# LSU_4_9_OpenAFR_Gauge.net
KiCad netlist of a schematic drawn in EAGLE
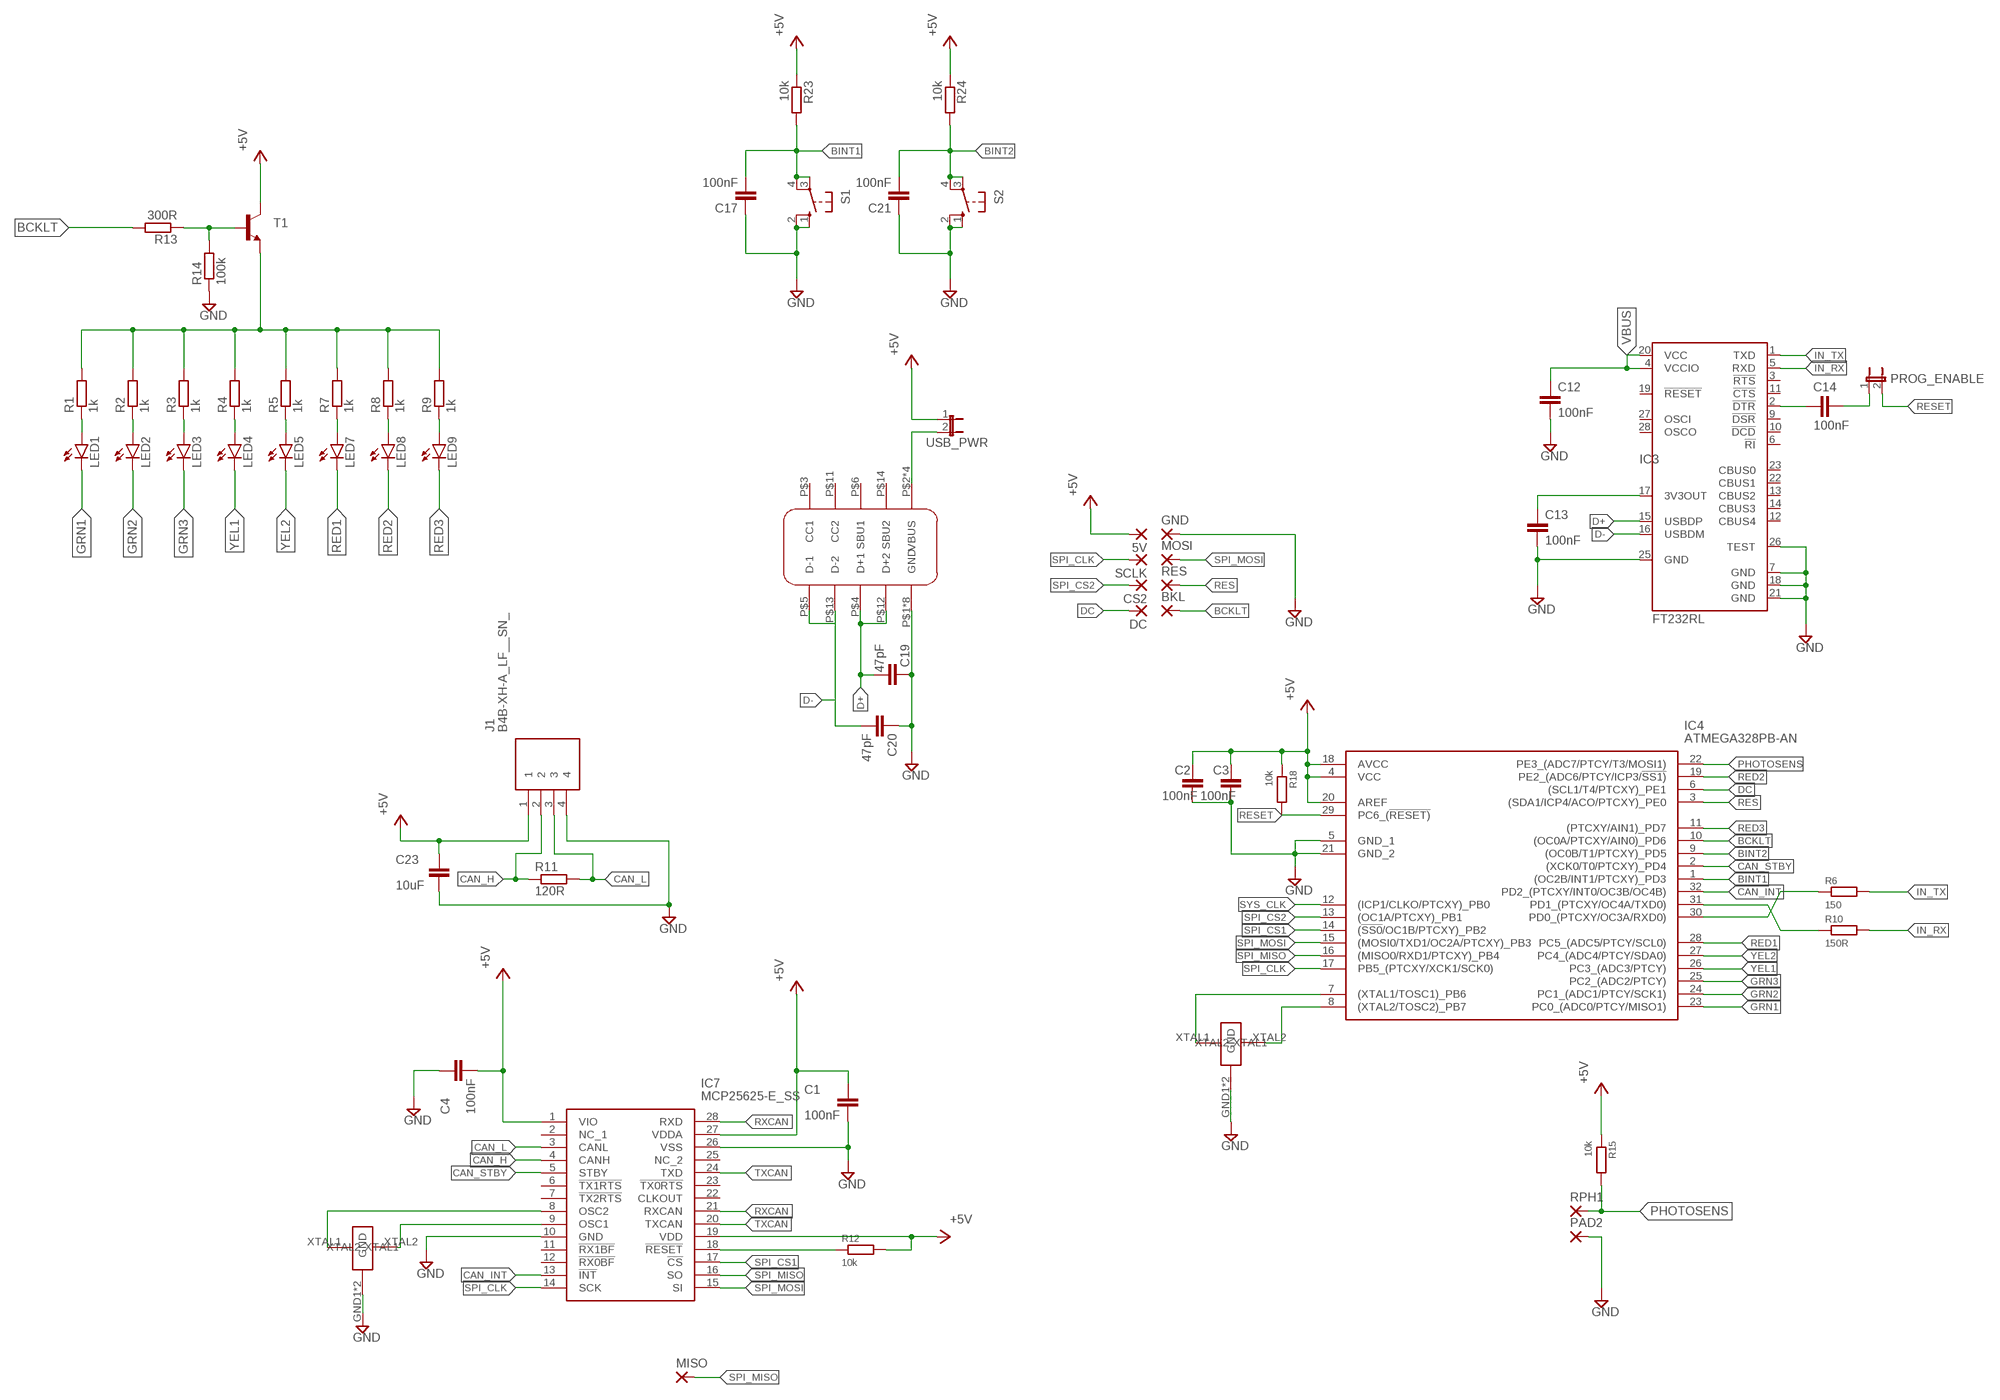
[diagram p0: schematic, sheet 1]

(export (version "E")
  (design (tool "Eeschema 10.0.6"))
  (components
    (comp (ref "5V")
      (value "1,6/0,9")
      (footprint "eagle-import:1,6_0,9")
      (libsource (lib "eagle-import") (part "1,6/0,9"))
    )
    (comp (ref "BKL")
      (value "1,6/0,9")
      (footprint "eagle-import:1,6_0,9")
      (libsource (lib "eagle-import") (part "1,6/0,9"))
    )
    (comp (ref "C1")
      (value "100nF")
      (footprint "eagle-import:C0805")
      (libsource (lib "eagle-import") (part "C-EUC0805"))
    )
    (comp (ref "C2")
      (value "100nF")
      (footprint "eagle-import:C0805")
      (libsource (lib "eagle-import") (part "C-EUC0805"))
    )
    (comp (ref "C3")
      (value "100nF")
      (footprint "eagle-import:C0805")
      (libsource (lib "eagle-import") (part "C-EUC0805"))
    )
    (comp (ref "C4")
      (value "100nF")
      (footprint "eagle-import:C0805")
      (libsource (lib "eagle-import") (part "C-EUC0805"))
    )
    (comp (ref "C12")
      (value "100nF")
      (footprint "eagle-import:C0805")
      (libsource (lib "eagle-import") (part "C-EUC0805"))
    )
    (comp (ref "C13")
      (value "100nF")
      (footprint "eagle-import:C0805")
      (libsource (lib "eagle-import") (part "C-EUC0805"))
    )
    (comp (ref "C14")
      (value "100nF")
      (footprint "eagle-import:C0805")
      (libsource (lib "eagle-import") (part "C-EUC0805"))
    )
    (comp (ref "C17")
      (value "100nF")
      (footprint "eagle-import:C0805")
      (libsource (lib "eagle-import") (part "C-EUC0805"))
    )
    (comp (ref "C19")
      (value "47pF")
      (footprint "eagle-import:C0805")
      (libsource (lib "eagle-import") (part "C-EUC0805"))
    )
    (comp (ref "C20")
      (value "47pF")
      (footprint "eagle-import:C0805")
      (libsource (lib "eagle-import") (part "C-EUC0805"))
    )
    (comp (ref "C21")
      (value "100nF")
      (footprint "eagle-import:C0805")
      (libsource (lib "eagle-import") (part "C-EUC0805"))
    )
    (comp (ref "C23")
      (value "10uF")
      (footprint "eagle-import:C0805")
      (libsource (lib "eagle-import") (part "C-EUC0805"))
    )
    (comp (ref "CS2")
      (value "1,6/0,9")
      (footprint "eagle-import:1,6_0,9")
      (libsource (lib "eagle-import") (part "1,6/0,9"))
    )
    (comp (ref "DC")
      (value "1,6/0,9")
      (footprint "eagle-import:1,6_0,9")
      (libsource (lib "eagle-import") (part "1,6/0,9"))
    )
    (comp (ref "GND")
      (value "1,6/0,9")
      (footprint "eagle-import:1,6_0,9")
      (libsource (lib "eagle-import") (part "1,6/0,9"))
    )
    (comp (ref "IC3")
      (value "FT232RL")
      (footprint "eagle-import:SSOP28")
      (libsource (lib "eagle-import") (part "FT232RL"))
    )
    (comp (ref "IC4")
      (value "ATMEGA328PB-AN")
      (footprint "eagle-import:QFP80P900X900X120-32N")
      (fields (field (name "MOUSER_PART_NUMBER") "556-ATMEGA328PB-AN"))
      (libsource (lib "eagle-import") (part "ATMEGA328PB-AN"))
    )
    (comp (ref "IC7")
      (value "MCP25625-E_SS")
      (footprint "eagle-import:SOP65P780X200-28N")
      (fields
        (field (name "MANUFACTURER_PART_NUMBER") "MCP25625-E/SS")
        (field (name "MOUSER_PART_NUMBER") "579-MCP25625-E/SS")
      )
      (libsource (lib "eagle-import") (part "MCP25625-E_SS"))
    )
    (comp (ref "J1")
      (value "B4B-XH-A_LF__SN_")
      (footprint "eagle-import:B4BXHALFSN")
      (fields
        (field (name "MANUFACTURER_PART_NUMBER") "B4B-XH-A(LF)(SN)")
        (field (name "MOUSER_PART_NUMBER") "306-B4BXHALFSN")
      )
      (libsource (lib "eagle-import") (part "B4B-XH-A_LF__SN_"))
    )
    (comp (ref "LED1")
      (value "LEDCHIPLED_1206")
      (footprint "eagle-import:CHIPLED_1206")
      (libsource (lib "eagle-import") (part "LEDCHIPLED_1206"))
    )
    (comp (ref "LED2")
      (value "LEDCHIPLED_1206")
      (footprint "eagle-import:CHIPLED_1206")
      (libsource (lib "eagle-import") (part "LEDCHIPLED_1206"))
    )
    (comp (ref "LED3")
      (value "LEDCHIPLED_1206")
      (footprint "eagle-import:CHIPLED_1206")
      (libsource (lib "eagle-import") (part "LEDCHIPLED_1206"))
    )
    (comp (ref "LED4")
      (value "LEDCHIPLED_1206")
      (footprint "eagle-import:CHIPLED_1206")
      (libsource (lib "eagle-import") (part "LEDCHIPLED_1206"))
    )
    (comp (ref "LED5")
      (value "LEDCHIPLED_1206")
      (footprint "eagle-import:CHIPLED_1206")
      (libsource (lib "eagle-import") (part "LEDCHIPLED_1206"))
    )
    (comp (ref "LED7")
      (value "LEDCHIPLED_1206")
      (footprint "eagle-import:CHIPLED_1206")
      (libsource (lib "eagle-import") (part "LEDCHIPLED_1206"))
    )
    (comp (ref "LED8")
      (value "LEDCHIPLED_1206")
      (footprint "eagle-import:CHIPLED_1206")
      (libsource (lib "eagle-import") (part "LEDCHIPLED_1206"))
    )
    (comp (ref "LED9")
      (value "LEDCHIPLED_1206")
      (footprint "eagle-import:CHIPLED_1206")
      (libsource (lib "eagle-import") (part "LEDCHIPLED_1206"))
    )
    (comp (ref "MISO")
      (value "1,6/0,9")
      (footprint "eagle-import:1,6_0,9")
      (libsource (lib "eagle-import") (part "1,6/0,9"))
    )
    (comp (ref "MOSI")
      (value "1,6/0,9")
      (footprint "eagle-import:1,6_0,9")
      (libsource (lib "eagle-import") (part "1,6/0,9"))
    )
    (comp (ref "PAD2")
      (value "1,6/0,8")
      (footprint "eagle-import:1,6_0,8")
      (libsource (lib "eagle-import") (part "1,6/0,8"))
    )
    (comp (ref "PROG_ENABLE")
      (value "JP1E")
      (footprint "eagle-import:JP1")
      (libsource (lib "eagle-import") (part "JP1E"))
    )
    (comp (ref "R1")
      (value "1k")
      (footprint "eagle-import:R0805")
      (libsource (lib "eagle-import") (part "R-EU_R0805"))
    )
    (comp (ref "R2")
      (value "1k")
      (footprint "eagle-import:R0805")
      (libsource (lib "eagle-import") (part "R-EU_R0805"))
    )
    (comp (ref "R3")
      (value "1k")
      (footprint "eagle-import:R0805")
      (libsource (lib "eagle-import") (part "R-EU_R0805"))
    )
    (comp (ref "R4")
      (value "1k")
      (footprint "eagle-import:R0805")
      (libsource (lib "eagle-import") (part "R-EU_R0805"))
    )
    (comp (ref "R5")
      (value "1k")
      (footprint "eagle-import:R0805")
      (libsource (lib "eagle-import") (part "R-EU_R0805"))
    )
    (comp (ref "R6")
      (value "150")
      (footprint "eagle-import:R0805")
      (libsource (lib "eagle-import") (part "R-EU_R0805"))
    )
    (comp (ref "R7")
      (value "1k")
      (footprint "eagle-import:R0805")
      (libsource (lib "eagle-import") (part "R-EU_R0805"))
    )
    (comp (ref "R8")
      (value "1k")
      (footprint "eagle-import:R0805")
      (libsource (lib "eagle-import") (part "R-EU_R0805"))
    )
    (comp (ref "R9")
      (value "1k")
      (footprint "eagle-import:R0805")
      (libsource (lib "eagle-import") (part "R-EU_R0805"))
    )
    (comp (ref "R10")
      (value "150R")
      (footprint "eagle-import:R0805")
      (libsource (lib "eagle-import") (part "R-EU_R0805"))
    )
    (comp (ref "R11")
      (value "120R")
      (footprint "eagle-import:R1206")
      (libsource (lib "eagle-import") (part "R-EU_R1206"))
    )
    (comp (ref "R12")
      (value "10k")
      (footprint "eagle-import:R0805")
      (libsource (lib "eagle-import") (part "R-EU_R0805"))
    )
    (comp (ref "R13")
      (value "300R")
      (footprint "eagle-import:R0805")
      (libsource (lib "eagle-import") (part "R-EU_R0805"))
    )
    (comp (ref "R14")
      (value "100k")
      (footprint "eagle-import:R0805")
      (libsource (lib "eagle-import") (part "R-EU_R0805"))
    )
    (comp (ref "R15")
      (value "10k")
      (footprint "eagle-import:R0805")
      (libsource (lib "eagle-import") (part "R-EU_R0805"))
    )
    (comp (ref "R18")
      (value "10k")
      (footprint "eagle-import:R0805")
      (libsource (lib "eagle-import") (part "R-EU_R0805"))
    )
    (comp (ref "R23")
      (value "10k")
      (footprint "eagle-import:R0805")
      (libsource (lib "eagle-import") (part "R-EU_R0805"))
    )
    (comp (ref "R24")
      (value "10k")
      (footprint "eagle-import:R0805")
      (libsource (lib "eagle-import") (part "R-EU_R0805"))
    )
    (comp (ref "RES")
      (value "1,6/0,9")
      (footprint "eagle-import:1,6_0,9")
      (libsource (lib "eagle-import") (part "1,6/0,9"))
    )
    (comp (ref "RPH1")
      (value "1,6/0,8")
      (footprint "eagle-import:1,6_0,8")
      (libsource (lib "eagle-import") (part "1,6/0,8"))
    )
    (comp (ref "S1")
      (value "10-XX")
      (footprint "eagle-import:B3F-10XX")
      (fields (field (name "MPN") "B3F-1000"))
      (libsource (lib "eagle-import") (part "10-XX"))
    )
    (comp (ref "S2")
      (value "10-XX")
      (footprint "eagle-import:B3F-10XX")
      (fields (field (name "MPN") "B3F-1000"))
      (libsource (lib "eagle-import") (part "10-XX"))
    )
    (comp (ref "SCLK")
      (value "1,6/0,9")
      (footprint "eagle-import:1,6_0,9")
      (libsource (lib "eagle-import") (part "1,6/0,9"))
    )
    (comp (ref "T1")
      (value "BC817-16-NPN-SOT23-BEC")
      (footprint "eagle-import:SOT23-BEC")
      (libsource (lib "eagle-import") (part "-NPN-SOT23-BECBC817-16"))
    )
    (comp (ref "U$1")
      (value "USBC-2.0-THT")
      (footprint "eagle-import:USBC-2.0-THT")
      (libsource (lib "eagle-import") (part "USBC-2.0-THT"))
    )
    (comp (ref "U$2")
      (value "E3X160181X04")
      (footprint "eagle-import:E3X160181X04")
      (libsource (lib "eagle-import") (part "E3X160181X04"))
    )
    (comp (ref "U$3")
      (value "E3X160181X04")
      (footprint "eagle-import:E3X160181X04")
      (libsource (lib "eagle-import") (part "E3X160181X04"))
    )
    (comp (ref "USB_PWR")
      (value "JP1E")
      (footprint "eagle-import:JP1")
      (libsource (lib "eagle-import") (part "JP1E"))
    )
  )
  (nets
    (net (code "1") (name "+5V") (class "Default")
      (node (ref "5V") (pin "1") (pinfunction "P_1") (pintype "passive"))
      (node (ref "C1") (pin "1") (pinfunction "1_1") (pintype "passive"))
      (node (ref "C2") (pin "1") (pinfunction "1_1") (pintype "passive"))
      (node (ref "C23") (pin "1") (pinfunction "1_1") (pintype "passive"))
      (node (ref "C3") (pin "1") (pinfunction "1_1") (pintype "passive"))
      (node (ref "C4") (pin "2") (pinfunction "2_2") (pintype "passive"))
      (node (ref "IC4") (pin "18") (pinfunction "AVCC_18") (pintype "bidirectional"))
      (node (ref "IC4") (pin "20") (pinfunction "AREF_20") (pintype "bidirectional"))
      (node (ref "IC4") (pin "4") (pinfunction "VCC_4") (pintype "bidirectional"))
      (node (ref "IC7") (pin "1") (pinfunction "VIO_1") (pintype "bidirectional"))
      (node (ref "IC7") (pin "19") (pinfunction "VDD_19") (pintype "bidirectional"))
      (node (ref "IC7") (pin "27") (pinfunction "VDDA_27") (pintype "bidirectional"))
      (node (ref "J1") (pin "1") (pinfunction "1_1") (pintype "bidirectional"))
      (node (ref "R12") (pin "2") (pinfunction "2_2") (pintype "passive"))
      (node (ref "R15") (pin "1") (pinfunction "1_1") (pintype "passive"))
      (node (ref "R18") (pin "1") (pinfunction "1_1") (pintype "passive"))
      (node (ref "R23") (pin "1") (pinfunction "1_1") (pintype "passive"))
      (node (ref "R24") (pin "1") (pinfunction "1_1") (pintype "passive"))
      (node (ref "T1") (pin "C") (pinfunction "C_C") (pintype "passive"))
      (node (ref "USB_PWR") (pin "1") (pinfunction "1_1") (pintype "passive"))
    )
    (net (code "2") (name "BCKLT") (class "Default")
      (node (ref "BKL") (pin "1") (pinfunction "P_1") (pintype "passive"))
      (node (ref "IC4") (pin "10") (pinfunction "(OC0A/PTCXY/AIN0)_PD6_10") (pintype "bidirectional"))
      (node (ref "R13") (pin "2") (pinfunction "2_2") (pintype "passive"))
    )
    (net (code "3") (name "BINT1") (class "Default")
      (node (ref "C17") (pin "2") (pinfunction "2_2") (pintype "passive"))
      (node (ref "IC4") (pin "1") (pinfunction "(OC2B/INT1/PTCXY)_PD3_1") (pintype "bidirectional"))
      (node (ref "R23") (pin "2") (pinfunction "2_2") (pintype "passive"))
      (node (ref "S1") (pin "3") (pinfunction "P_3") (pintype "passive"))
      (node (ref "S1") (pin "4") (pinfunction "P1_4") (pintype "passive"))
    )
    (net (code "4") (name "BINT2") (class "Default")
      (node (ref "C21") (pin "2") (pinfunction "2_2") (pintype "passive"))
      (node (ref "IC4") (pin "9") (pinfunction "(OC0B/T1/PTCXY)_PD5_9") (pintype "bidirectional"))
      (node (ref "R24") (pin "2") (pinfunction "2_2") (pintype "passive"))
      (node (ref "S2") (pin "3") (pinfunction "P_3") (pintype "passive"))
      (node (ref "S2") (pin "4") (pinfunction "P1_4") (pintype "passive"))
    )
    (net (code "5") (name "CAN_H") (class "Default")
      (node (ref "IC7") (pin "4") (pinfunction "CANH_4") (pintype "bidirectional"))
      (node (ref "J1") (pin "2") (pinfunction "2_2") (pintype "bidirectional"))
      (node (ref "R11") (pin "1") (pinfunction "1_1") (pintype "passive"))
    )
    (net (code "6") (name "CAN_INT") (class "Default")
      (node (ref "IC4") (pin "32") (pinfunction "PD2_(PTCXY/INT0/OC3B/OC4B)_32") (pintype "bidirectional"))
      (node (ref "IC7") (pin "13") (pinfunction "~{INT}_13") (pintype "bidirectional"))
    )
    (net (code "7") (name "CAN_L") (class "Default")
      (node (ref "IC7") (pin "3") (pinfunction "CANL_3") (pintype "bidirectional"))
      (node (ref "J1") (pin "3") (pinfunction "3_3") (pintype "bidirectional"))
      (node (ref "R11") (pin "2") (pinfunction "2_2") (pintype "passive"))
    )
    (net (code "8") (name "CAN_STBY") (class "Default")
      (node (ref "IC4") (pin "2") (pinfunction "(XCK0/T0/PTCXY)_PD4_2") (pintype "bidirectional"))
      (node (ref "IC7") (pin "5") (pinfunction "STBY_5") (pintype "bidirectional"))
    )
    (net (code "9") (name "D+") (class "Default")
      (node (ref "C19") (pin "2") (pinfunction "2_2") (pintype "passive"))
      (node (ref "IC3") (pin "15") (pinfunction "USBDP_15") (pintype "bidirectional"))
      (node (ref "U$1") (pin "P$12") (pinfunction "D+2_P$12") (pintype "bidirectional"))
      (node (ref "U$1") (pin "P$4") (pinfunction "D+1_P$4") (pintype "bidirectional"))
    )
    (net (code "10") (name "D-") (class "Default")
      (node (ref "C20") (pin "2") (pinfunction "2_2") (pintype "passive"))
      (node (ref "IC3") (pin "16") (pinfunction "USBDM_16") (pintype "bidirectional"))
      (node (ref "U$1") (pin "P$13") (pinfunction "D-2_P$13") (pintype "bidirectional"))
      (node (ref "U$1") (pin "P$5") (pinfunction "D-1_P$5") (pintype "bidirectional"))
    )
    (net (code "11") (name "DC") (class "Default")
      (node (ref "DC") (pin "1") (pinfunction "P_1") (pintype "passive"))
      (node (ref "IC4") (pin "6") (pinfunction "(SCL1/T4/PTCXY)_PE1_6") (pintype "bidirectional"))
    )
    (net (code "12") (name "GND") (class "Default")
      (node (ref "C1") (pin "2") (pinfunction "2_2") (pintype "passive"))
      (node (ref "C12") (pin "2") (pinfunction "2_2") (pintype "passive"))
      (node (ref "C13") (pin "2") (pinfunction "2_2") (pintype "passive"))
      (node (ref "C17") (pin "1") (pinfunction "1_1") (pintype "passive"))
      (node (ref "C19") (pin "1") (pinfunction "1_1") (pintype "passive"))
      (node (ref "C2") (pin "2") (pinfunction "2_2") (pintype "passive"))
      (node (ref "C20") (pin "1") (pinfunction "1_1") (pintype "passive"))
      (node (ref "C21") (pin "1") (pinfunction "1_1") (pintype "passive"))
      (node (ref "C23") (pin "2") (pinfunction "2_2") (pintype "passive"))
      (node (ref "C3") (pin "2") (pinfunction "2_2") (pintype "passive"))
      (node (ref "C4") (pin "1") (pinfunction "1_1") (pintype "passive"))
      (node (ref "GND") (pin "1") (pinfunction "P_1") (pintype "passive"))
      (node (ref "IC3") (pin "18") (pinfunction "GND_18") (pintype "power_in"))
      (node (ref "IC3") (pin "21") (pinfunction "GND_21") (pintype "power_in"))
      (node (ref "IC3") (pin "25") (pinfunction "GND_25") (pintype "power_in"))
      (node (ref "IC3") (pin "26") (pinfunction "TEST_26") (pintype "input"))
      (node (ref "IC3") (pin "7") (pinfunction "GND_7") (pintype "power_in"))
      (node (ref "IC4") (pin "21") (pinfunction "GND_2_21") (pintype "bidirectional"))
      (node (ref "IC4") (pin "5") (pinfunction "GND_1_5") (pintype "bidirectional"))
      (node (ref "IC7") (pin "10") (pinfunction "GND_10") (pintype "bidirectional"))
      (node (ref "IC7") (pin "26") (pinfunction "VSS_26") (pintype "bidirectional"))
      (node (ref "J1") (pin "4") (pinfunction "4_4") (pintype "bidirectional"))
      (node (ref "PAD2") (pin "1") (pinfunction "P_1") (pintype "passive"))
      (node (ref "R14") (pin "1") (pinfunction "1_1") (pintype "passive"))
      (node (ref "S1") (pin "1") (pinfunction "S_1") (pintype "passive"))
      (node (ref "S1") (pin "2") (pinfunction "S1_2") (pintype "passive"))
      (node (ref "S2") (pin "1") (pinfunction "S_1") (pintype "passive"))
      (node (ref "S2") (pin "2") (pinfunction "S1_2") (pintype "passive"))
      (node (ref "U$1") (pin "P$1") (pinfunction "GND_P$1") (pintype "bidirectional"))
      (node (ref "U$1") (pin "P$16") (pinfunction "GND_P$16") (pintype "bidirectional"))
      (node (ref "U$1") (pin "P$17") (pinfunction "GND_P$17") (pintype "bidirectional"))
      (node (ref "U$1") (pin "P$18") (pinfunction "GND_P$18") (pintype "bidirectional"))
      (node (ref "U$1") (pin "P$19") (pinfunction "GND_P$19") (pintype "bidirectional"))
      (node (ref "U$1") (pin "P$20") (pinfunction "GND_P$20") (pintype "bidirectional"))
      (node (ref "U$1") (pin "P$8") (pinfunction "GND_P$8") (pintype "bidirectional"))
      (node (ref "U$1") (pin "P$9") (pinfunction "GND_P$9") (pintype "bidirectional"))
      (node (ref "U$2") (pin "GND1") (pinfunction "GND_GND1") (pintype "bidirectional"))
      (node (ref "U$2") (pin "GND2") (pinfunction "GND_GND2") (pintype "bidirectional"))
      (node (ref "U$3") (pin "GND1") (pinfunction "GND_GND1") (pintype "bidirectional"))
      (node (ref "U$3") (pin "GND2") (pinfunction "GND_GND2") (pintype "bidirectional"))
    )
    (net (code "13") (name "GRN1") (class "Default")
      (node (ref "IC4") (pin "23") (pinfunction "PC0_(ADC0/PTCY/MISO1)_23") (pintype "bidirectional"))
      (node (ref "LED1") (pin "C") (pinfunction "C_C") (pintype "passive"))
    )
    (net (code "14") (name "GRN2") (class "Default")
      (node (ref "IC4") (pin "24") (pinfunction "PC1_(ADC1/PTCY/SCK1)_24") (pintype "bidirectional"))
      (node (ref "LED2") (pin "C") (pinfunction "C_C") (pintype "passive"))
    )
    (net (code "15") (name "GRN3") (class "Default")
      (node (ref "IC4") (pin "25") (pinfunction "PC2_(ADC2/PTCY)_25") (pintype "bidirectional"))
      (node (ref "LED3") (pin "C") (pinfunction "C_C") (pintype "passive"))
    )
    (net (code "16") (name "IN_RX") (class "Default")
      (node (ref "IC3") (pin "5") (pinfunction "RXD_5") (pintype "input"))
      (node (ref "R10") (pin "2") (pinfunction "2_2") (pintype "passive"))
    )
    (net (code "17") (name "IN_TX") (class "Default")
      (node (ref "IC3") (pin "1") (pinfunction "TXD_1") (pintype "output"))
      (node (ref "R6") (pin "2") (pinfunction "2_2") (pintype "passive"))
    )
    (net (code "18") (name "Net-(C14-Pad2)") (class "Default")
      (node (ref "C14") (pin "2") (pinfunction "2_2") (pintype "passive"))
      (node (ref "PROG_ENABLE") (pin "1") (pinfunction "1_1") (pintype "passive"))
    )
    (net (code "19") (name "Net-(IC3-3V3OUT)") (class "Default")
      (node (ref "C13") (pin "1") (pinfunction "1_1") (pintype "passive"))
      (node (ref "IC3") (pin "17") (pinfunction "3V3OUT_17") (pintype "output"))
    )
    (net (code "20") (name "Net-(IC3-~{DTR})") (class "Default")
      (node (ref "C14") (pin "1") (pinfunction "1_1") (pintype "passive"))
      (node (ref "IC3") (pin "2") (pinfunction "~{DTR}_2") (pintype "output"))
    )
    (net (code "21") (name "Net-(IC4-(XTAL1{slash}TOSC1)_PB6)") (class "Default")
      (node (ref "IC4") (pin "7") (pinfunction "(XTAL1/TOSC1)_PB6_7") (pintype "bidirectional"))
      (node (ref "U$3") (pin "XTAL1") (pinfunction "XTAL1_XTAL1") (pintype "bidirectional"))
    )
    (net (code "22") (name "Net-(IC4-(XTAL2{slash}TOSC2)_PB7)") (class "Default")
      (node (ref "IC4") (pin "8") (pinfunction "(XTAL2/TOSC2)_PB7_8") (pintype "bidirectional"))
      (node (ref "U$3") (pin "XTAL2") (pinfunction "XTAL2_XTAL2") (pintype "bidirectional"))
    )
    (net (code "23") (name "Net-(IC4-PD0_(PTCXY{slash}OC3A{slash}RXD0))") (class "Default")
      (node (ref "IC4") (pin "30") (pinfunction "PD0_(PTCXY/OC3A/RXD0)_30") (pintype "bidirectional"))
      (node (ref "R6") (pin "1") (pinfunction "1_1") (pintype "passive"))
    )
    (net (code "24") (name "Net-(IC4-PD1_(PTCXY{slash}OC4A{slash}TXD0))") (class "Default")
      (node (ref "IC4") (pin "31") (pinfunction "PD1_(PTCXY/OC4A/TXD0)_31") (pintype "bidirectional"))
      (node (ref "R10") (pin "1") (pinfunction "1_1") (pintype "passive"))
    )
    (net (code "25") (name "Net-(IC7-OSC1)") (class "Default")
      (node (ref "IC7") (pin "9") (pinfunction "OSC1_9") (pintype "bidirectional"))
      (node (ref "U$2") (pin "XTAL2") (pinfunction "XTAL2_XTAL2") (pintype "bidirectional"))
    )
    (net (code "26") (name "Net-(IC7-OSC2)") (class "Default")
      (node (ref "IC7") (pin "8") (pinfunction "OSC2_8") (pintype "bidirectional"))
      (node (ref "U$2") (pin "XTAL1") (pinfunction "XTAL1_XTAL1") (pintype "bidirectional"))
    )
    (net (code "27") (name "Net-(IC7-~{RESET})") (class "Default")
      (node (ref "IC7") (pin "18") (pinfunction "~{RESET}_18") (pintype "bidirectional"))
      (node (ref "R12") (pin "1") (pinfunction "1_1") (pintype "passive"))
    )
    (net (code "28") (name "Net-(LED1-PadA)") (class "Default")
      (node (ref "LED1") (pin "A") (pinfunction "A_A") (pintype "passive"))
      (node (ref "R1") (pin "1") (pinfunction "1_1") (pintype "passive"))
    )
    (net (code "29") (name "Net-(LED2-PadA)") (class "Default")
      (node (ref "LED2") (pin "A") (pinfunction "A_A") (pintype "passive"))
      (node (ref "R2") (pin "1") (pinfunction "1_1") (pintype "passive"))
    )
    (net (code "30") (name "Net-(LED3-PadA)") (class "Default")
      (node (ref "LED3") (pin "A") (pinfunction "A_A") (pintype "passive"))
      (node (ref "R3") (pin "1") (pinfunction "1_1") (pintype "passive"))
    )
    (net (code "31") (name "Net-(LED4-PadA)") (class "Default")
      (node (ref "LED4") (pin "A") (pinfunction "A_A") (pintype "passive"))
      (node (ref "R4") (pin "1") (pinfunction "1_1") (pintype "passive"))
    )
    (net (code "32") (name "Net-(LED5-PadA)") (class "Default")
      (node (ref "LED5") (pin "A") (pinfunction "A_A") (pintype "passive"))
      (node (ref "R5") (pin "1") (pinfunction "1_1") (pintype "passive"))
    )
    (net (code "33") (name "Net-(LED7-PadA)") (class "Default")
      (node (ref "LED7") (pin "A") (pinfunction "A_A") (pintype "passive"))
      (node (ref "R7") (pin "1") (pinfunction "1_1") (pintype "passive"))
    )
    (net (code "34") (name "Net-(LED8-PadA)") (class "Default")
      (node (ref "LED8") (pin "A") (pinfunction "A_A") (pintype "passive"))
      (node (ref "R8") (pin "1") (pinfunction "1_1") (pintype "passive"))
    )
    (net (code "35") (name "Net-(LED9-PadA)") (class "Default")
      (node (ref "LED9") (pin "A") (pinfunction "A_A") (pintype "passive"))
      (node (ref "R9") (pin "1") (pinfunction "1_1") (pintype "passive"))
    )
    (net (code "36") (name "Net-(R1-Pad2)") (class "Default")
      (node (ref "R1") (pin "2") (pinfunction "2_2") (pintype "passive"))
      (node (ref "R2") (pin "2") (pinfunction "2_2") (pintype "passive"))
      (node (ref "R3") (pin "2") (pinfunction "2_2") (pintype "passive"))
      (node (ref "R4") (pin "2") (pinfunction "2_2") (pintype "passive"))
      (node (ref "R5") (pin "2") (pinfunction "2_2") (pintype "passive"))
      (node (ref "R7") (pin "2") (pinfunction "2_2") (pintype "passive"))
      (node (ref "R8") (pin "2") (pinfunction "2_2") (pintype "passive"))
      (node (ref "R9") (pin "2") (pinfunction "2_2") (pintype "passive"))
      (node (ref "T1") (pin "E") (pinfunction "E_E") (pintype "passive"))
    )
    (net (code "37") (name "Net-(R13-Pad1)") (class "Default")
      (node (ref "R13") (pin "1") (pinfunction "1_1") (pintype "passive"))
      (node (ref "R14") (pin "2") (pinfunction "2_2") (pintype "passive"))
      (node (ref "T1") (pin "B") (pinfunction "B_B") (pintype "passive"))
    )
    (net (code "38") (name "PHOTOSENS") (class "Default")
      (node (ref "IC4") (pin "22") (pinfunction "PE3_(ADC7/PTCY/T3/MOSI1)_22") (pintype "bidirectional"))
      (node (ref "R15") (pin "2") (pinfunction "2_2") (pintype "passive"))
      (node (ref "RPH1") (pin "1") (pinfunction "P_1") (pintype "passive"))
    )
    (net (code "39") (name "RED1") (class "Default")
      (node (ref "IC4") (pin "28") (pinfunction "PC5_(ADC5/PTCY/SCL0)_28") (pintype "bidirectional"))
      (node (ref "LED7") (pin "C") (pinfunction "C_C") (pintype "passive"))
    )
    (net (code "40") (name "RED2") (class "Default")
      (node (ref "IC4") (pin "19") (pinfunction "PE2_(ADC6/PTCY/ICP3/~{SS1})_19") (pintype "bidirectional"))
      (node (ref "LED8") (pin "C") (pinfunction "C_C") (pintype "passive"))
    )
    (net (code "41") (name "RED3") (class "Default")
      (node (ref "IC4") (pin "11") (pinfunction "(PTCXY/AIN1)_PD7_11") (pintype "bidirectional"))
      (node (ref "LED9") (pin "C") (pinfunction "C_C") (pintype "passive"))
    )
    (net (code "42") (name "RES") (class "Default")
      (node (ref "IC4") (pin "3") (pinfunction "(SDA1/ICP4/ACO/PTCXY)_PE0_3") (pintype "bidirectional"))
      (node (ref "RES") (pin "1") (pinfunction "P_1") (pintype "passive"))
    )
    (net (code "43") (name "RESET") (class "Default")
      (node (ref "IC4") (pin "29") (pinfunction "PC6_(~{RESET})_29") (pintype "bidirectional"))
      (node (ref "PROG_ENABLE") (pin "2") (pinfunction "2_2") (pintype "passive"))
      (node (ref "R18") (pin "2") (pinfunction "2_2") (pintype "passive"))
    )
    (net (code "44") (name "RXCAN") (class "Default")
      (node (ref "IC7") (pin "21") (pinfunction "RXCAN_21") (pintype "bidirectional"))
      (node (ref "IC7") (pin "28") (pinfunction "RXD_28") (pintype "bidirectional"))
    )
    (net (code "45") (name "SPI_CLK") (class "Default")
      (node (ref "IC4") (pin "17") (pinfunction "PB5_(PTCXY/XCK1/SCK0)_17") (pintype "bidirectional"))
      (node (ref "IC7") (pin "14") (pinfunction "SCK_14") (pintype "bidirectional"))
      (node (ref "SCLK") (pin "1") (pinfunction "P_1") (pintype "passive"))
    )
    (net (code "46") (name "SPI_CS1") (class "Default")
      (node (ref "IC4") (pin "14") (pinfunction "(~{SS0}/OC1B/PTCXY)_PB2_14") (pintype "bidirectional"))
      (node (ref "IC7") (pin "17") (pinfunction "~{CS}_17") (pintype "bidirectional"))
    )
    (net (code "47") (name "SPI_CS2") (class "Default")
      (node (ref "CS2") (pin "1") (pinfunction "P_1") (pintype "passive"))
      (node (ref "IC4") (pin "13") (pinfunction "(OC1A/PTCXY)_PB1_13") (pintype "bidirectional"))
    )
    (net (code "48") (name "SPI_MISO") (class "Default")
      (node (ref "IC4") (pin "16") (pinfunction "(MISO0/RXD1/PTCXY)_PB4_16") (pintype "bidirectional"))
      (node (ref "IC7") (pin "16") (pinfunction "SO_16") (pintype "bidirectional"))
      (node (ref "MISO") (pin "1") (pinfunction "P_1") (pintype "passive"))
    )
    (net (code "49") (name "SPI_MOSI") (class "Default")
      (node (ref "IC4") (pin "15") (pinfunction "(MOSI0/TXD1/OC2A/PTCXY)_PB3_15") (pintype "bidirectional"))
      (node (ref "IC7") (pin "15") (pinfunction "SI_15") (pintype "bidirectional"))
      (node (ref "MOSI") (pin "1") (pinfunction "P_1") (pintype "passive"))
    )
    (net (code "50") (name "SYS_CLK") (class "Default")
      (node (ref "IC4") (pin "12") (pinfunction "(ICP1/CLKO/PTCXY)_PB0_12") (pintype "bidirectional"))
    )
    (net (code "51") (name "TXCAN") (class "Default")
      (node (ref "IC7") (pin "20") (pinfunction "TXCAN_20") (pintype "bidirectional"))
      (node (ref "IC7") (pin "24") (pinfunction "TXD_24") (pintype "bidirectional"))
    )
    (net (code "52") (name "VBUS") (class "Default")
      (node (ref "C12") (pin "1") (pinfunction "1_1") (pintype "passive"))
      (node (ref "IC3") (pin "20") (pinfunction "VCC_20") (pintype "power_in"))
      (node (ref "IC3") (pin "4") (pinfunction "VCCIO_4") (pintype "power_in"))
      (node (ref "U$1") (pin "P$10") (pinfunction "VBUS_P$10") (pintype "bidirectional"))
      (node (ref "U$1") (pin "P$15") (pinfunction "VBUS_P$15") (pintype "bidirectional"))
      (node (ref "U$1") (pin "P$2") (pinfunction "VBUS_P$2") (pintype "bidirectional"))
      (node (ref "U$1") (pin "P$7") (pinfunction "VBUS_P$7") (pintype "bidirectional"))
      (node (ref "USB_PWR") (pin "2") (pinfunction "2_2") (pintype "passive"))
    )
    (net (code "53") (name "YEL1") (class "Default")
      (node (ref "IC4") (pin "26") (pinfunction "PC3_(ADC3/PTCY)_26") (pintype "bidirectional"))
      (node (ref "LED4") (pin "C") (pinfunction "C_C") (pintype "passive"))
    )
    (net (code "54") (name "YEL2") (class "Default")
      (node (ref "IC4") (pin "27") (pinfunction "PC4_(ADC4/PTCY/SDA0)_27") (pintype "bidirectional"))
      (node (ref "LED5") (pin "C") (pinfunction "C_C") (pintype "passive"))
    )
    (net (code "55") (name "unconnected-(IC3-CBUS0-Pad23)") (class "Default")
      (node (ref "IC3") (pin "23") (pinfunction "CBUS0_23") (pintype "bidirectional"))
    )
    (net (code "56") (name "unconnected-(IC3-CBUS1-Pad22)") (class "Default")
      (node (ref "IC3") (pin "22") (pinfunction "CBUS1_22") (pintype "bidirectional"))
    )
    (net (code "57") (name "unconnected-(IC3-CBUS2-Pad13)") (class "Default")
      (node (ref "IC3") (pin "13") (pinfunction "CBUS2_13") (pintype "bidirectional"))
    )
    (net (code "58") (name "unconnected-(IC3-CBUS3-Pad14)") (class "Default")
      (node (ref "IC3") (pin "14") (pinfunction "CBUS3_14") (pintype "bidirectional"))
    )
    (net (code "59") (name "unconnected-(IC3-CBUS4-Pad12)") (class "Default")
      (node (ref "IC3") (pin "12") (pinfunction "CBUS4_12") (pintype "bidirectional"))
    )
    (net (code "60") (name "unconnected-(IC3-OSCI-Pad27)") (class "Default")
      (node (ref "IC3") (pin "27") (pinfunction "OSCI_27") (pintype "input"))
    )
    (net (code "61") (name "unconnected-(IC3-OSCO-Pad28)") (class "Default")
      (node (ref "IC3") (pin "28") (pinfunction "OSCO_28") (pintype "output"))
    )
    (net (code "62") (name "unconnected-(IC3-~{CTS}-Pad11)") (class "Default")
      (node (ref "IC3") (pin "11") (pinfunction "~{CTS}_11") (pintype "input"))
    )
    (net (code "63") (name "unconnected-(IC3-~{DCD}-Pad10)") (class "Default")
      (node (ref "IC3") (pin "10") (pinfunction "~{DCD}_10") (pintype "input"))
    )
    (net (code "64") (name "unconnected-(IC3-~{DSR}-Pad9)") (class "Default")
      (node (ref "IC3") (pin "9") (pinfunction "~{DSR}_9") (pintype "input"))
    )
    (net (code "65") (name "unconnected-(IC3-~{RESET}-Pad19)") (class "Default")
      (node (ref "IC3") (pin "19") (pinfunction "~{RESET}_19") (pintype "input"))
    )
    (net (code "66") (name "unconnected-(IC3-~{RI}-Pad6)") (class "Default")
      (node (ref "IC3") (pin "6") (pinfunction "~{RI}_6") (pintype "input"))
    )
    (net (code "67") (name "unconnected-(IC3-~{RTS}-Pad3)") (class "Default")
      (node (ref "IC3") (pin "3") (pinfunction "~{RTS}_3") (pintype "output"))
    )
    (net (code "68") (name "unconnected-(IC7-CLKOUT-Pad22)") (class "Default")
      (node (ref "IC7") (pin "22") (pinfunction "CLKOUT_22") (pintype "bidirectional"))
    )
    (net (code "69") (name "unconnected-(IC7-NC_1-Pad2)") (class "Default")
      (node (ref "IC7") (pin "2") (pinfunction "NC_1_2") (pintype "bidirectional"))
    )
    (net (code "70") (name "unconnected-(IC7-NC_2-Pad25)") (class "Default")
      (node (ref "IC7") (pin "25") (pinfunction "NC_2_25") (pintype "bidirectional"))
    )
    (net (code "71") (name "unconnected-(IC7-~{RX0BF}-Pad12)") (class "Default")
      (node (ref "IC7") (pin "12") (pinfunction "~{RX0BF}_12") (pintype "bidirectional"))
    )
    (net (code "72") (name "unconnected-(IC7-~{RX1BF}-Pad11)") (class "Default")
      (node (ref "IC7") (pin "11") (pinfunction "~{RX1BF}_11") (pintype "bidirectional"))
    )
    (net (code "73") (name "unconnected-(IC7-~{TX0RTS}-Pad23)") (class "Default")
      (node (ref "IC7") (pin "23") (pinfunction "~{TX0RTS}_23") (pintype "bidirectional"))
    )
    (net (code "74") (name "unconnected-(IC7-~{TX1RTS}-Pad6)") (class "Default")
      (node (ref "IC7") (pin "6") (pinfunction "~{TX1RTS}_6") (pintype "bidirectional"))
    )
    (net (code "75") (name "unconnected-(IC7-~{TX2RTS}-Pad7)") (class "Default")
      (node (ref "IC7") (pin "7") (pinfunction "~{TX2RTS}_7") (pintype "bidirectional"))
    )
    (net (code "76") (name "unconnected-(U$1-CC1-PadP$3)") (class "Default")
      (node (ref "U$1") (pin "P$3") (pinfunction "CC1_P$3") (pintype "bidirectional"))
    )
    (net (code "77") (name "unconnected-(U$1-CC2-PadP$11)") (class "Default")
      (node (ref "U$1") (pin "P$11") (pinfunction "CC2_P$11") (pintype "bidirectional"))
    )
    (net (code "78") (name "unconnected-(U$1-SBU1-PadP$6)") (class "Default")
      (node (ref "U$1") (pin "P$6") (pinfunction "SBU1_P$6") (pintype "bidirectional"))
    )
    (net (code "79") (name "unconnected-(U$1-SBU2-PadP$14)") (class "Default")
      (node (ref "U$1") (pin "P$14") (pinfunction "SBU2_P$14") (pintype "bidirectional"))
    )
  )
)
